# door_light.net
KiCad netlist of a schematic drawn in EAGLE
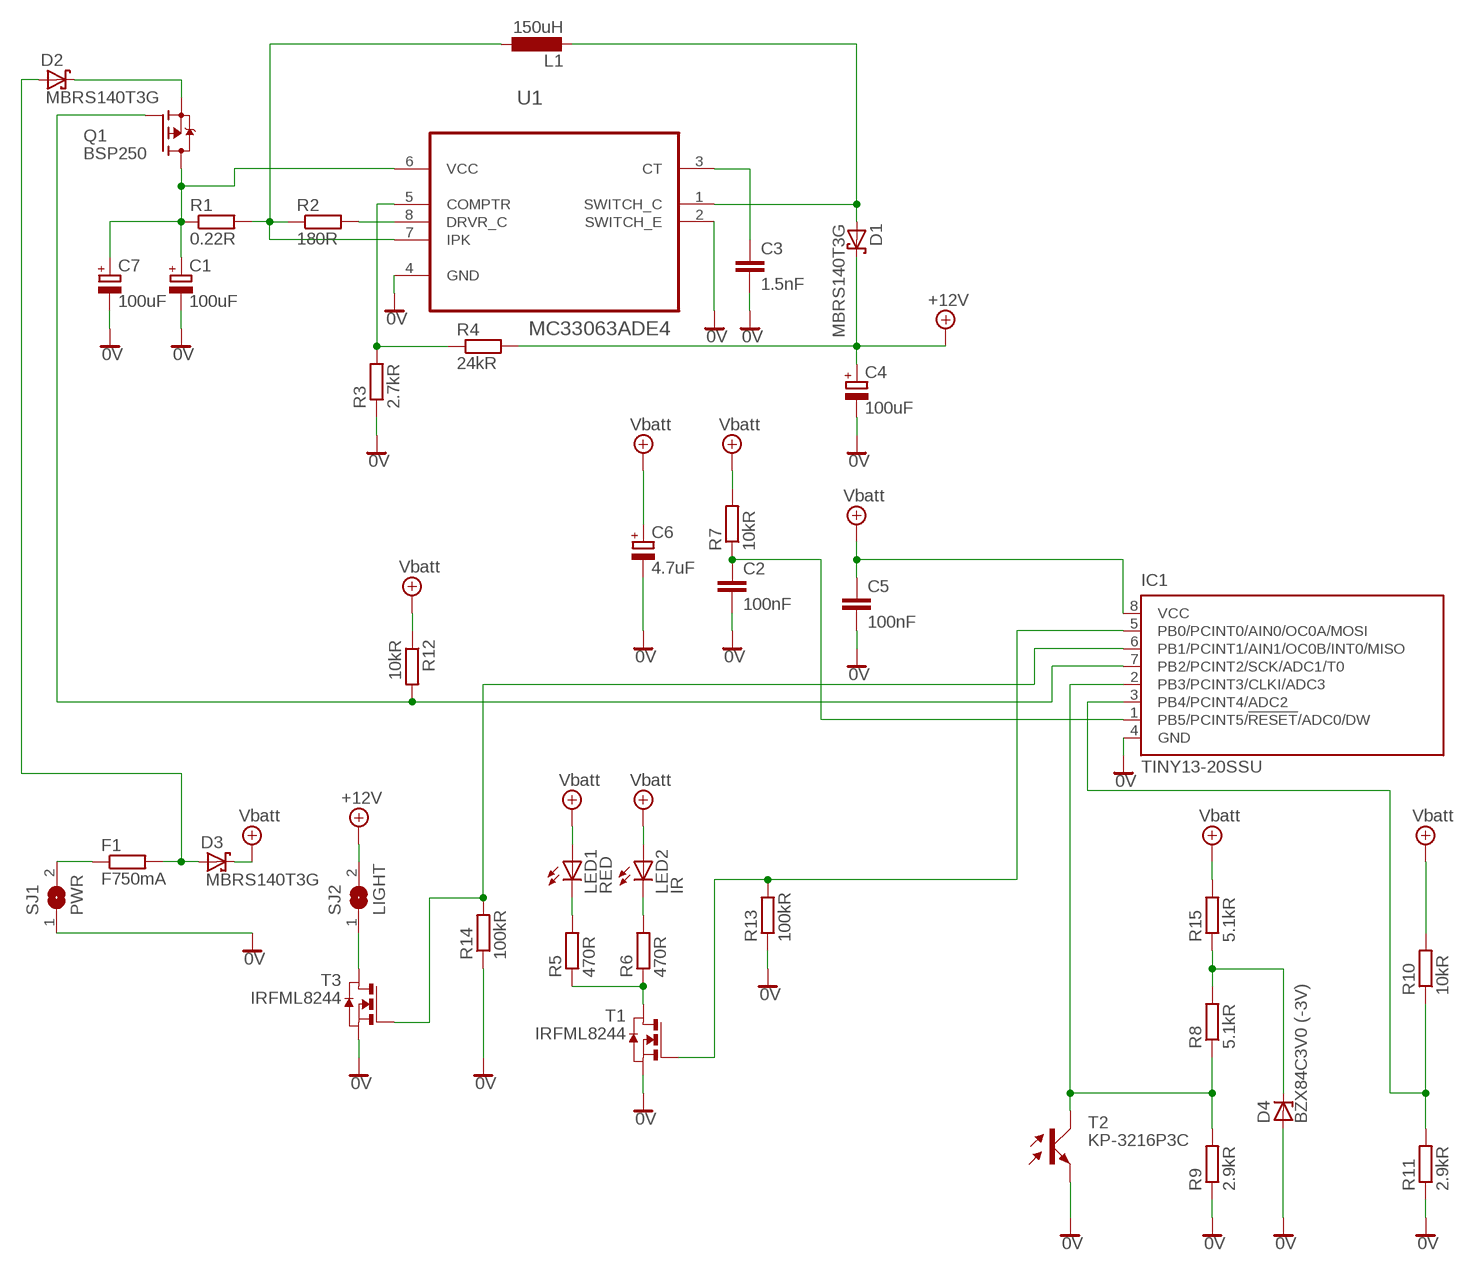
[diagram p0: schematic, sheet 1]

(export (version "E")
  (design (tool "Eeschema 10.0.6"))
  (components
    (comp (ref "C1")
      (value "100uF")
      (footprint "eagle-import:153CLV-0810")
      (libsource (lib "eagle-import") (part "CPOL-EU153CLV-0810"))
    )
    (comp (ref "C2")
      (value "100nF")
      (footprint "eagle-import:C1206")
      (libsource (lib "eagle-import") (part "C-EUC1206"))
    )
    (comp (ref "C3")
      (value "1.5nF")
      (footprint "eagle-import:C1206")
      (libsource (lib "eagle-import") (part "C-EUC1206"))
    )
    (comp (ref "C4")
      (value "100uF")
      (footprint "eagle-import:153CLV-0810")
      (libsource (lib "eagle-import") (part "CPOL-EU153CLV-0810"))
    )
    (comp (ref "C5")
      (value "100nF")
      (footprint "eagle-import:C1206")
      (libsource (lib "eagle-import") (part "C-EUC1206"))
    )
    (comp (ref "C6")
      (value "4.7uF")
      (footprint "eagle-import:153CLV-0405")
      (libsource (lib "eagle-import") (part "CPOL-EU153CLV-0405"))
    )
    (comp (ref "C7")
      (value "100uF")
      (footprint "eagle-import:153CLV-0810")
      (libsource (lib "eagle-import") (part "CPOL-EU153CLV-0810"))
    )
    (comp (ref "D1")
      (value "MBRS140T3G")
      (footprint "eagle-import:SMB")
      (libsource (lib "eagle-import") (part "MBRS130LT3"))
    )
    (comp (ref "D2")
      (value "MBRS140T3G")
      (footprint "eagle-import:SMB")
      (libsource (lib "eagle-import") (part "MBRS130LT3"))
    )
    (comp (ref "D3")
      (value "MBRS140T3G")
      (footprint "eagle-import:SMB")
      (libsource (lib "eagle-import") (part "MBRS130LT3"))
    )
    (comp (ref "D4")
      (value "BZX84C3V0 (-3V)")
      (footprint "eagle-import:TO236")
      (libsource (lib "eagle-import") (part "BZX84CSMD"))
    )
    (comp (ref "F1")
      (value "F750mA")
      (footprint "eagle-import:MINI_MELF-0207W")
      (libsource (lib "eagle-import") (part "R-EU_MELF0207W"))
    )
    (comp (ref "IC1")
      (value "TINY13-20SSU")
      (footprint "eagle-import:8S1")
      (fields (field (name "MPN") "ATTINY13-20SSU"))
      (libsource (lib "eagle-import") (part "TINY13SSU-20"))
    )
    (comp (ref "L1")
      (value "150uH")
      (footprint "eagle-import:PIS2816")
      (libsource (lib "eagle-import") (part "L-EUPIS2816"))
    )
    (comp (ref "LED1")
      (value "RED")
      (footprint "eagle-import:CHIPLED_0603")
      (libsource (lib "eagle-import") (part "LEDCHIPLED_0603"))
    )
    (comp (ref "LED2")
      (value "IR")
      (footprint "eagle-import:CHIPLED_1206")
      (libsource (lib "eagle-import") (part "LEDCHIPLED_1206"))
    )
    (comp (ref "Q1")
      (value "BSP250")
      (footprint "eagle-import:SOT223")
      (libsource (lib "eagle-import") (part "BSP170P"))
    )
    (comp (ref "R1")
      (value "0.22R")
      (footprint "eagle-import:M1206")
      (libsource (lib "eagle-import") (part "R-EU_M1206"))
    )
    (comp (ref "R2")
      (value "180R")
      (footprint "eagle-import:R0603")
      (libsource (lib "eagle-import") (part "R-EU_R0603"))
    )
    (comp (ref "R3")
      (value "2.7kR")
      (footprint "eagle-import:R0603")
      (libsource (lib "eagle-import") (part "R-EU_R0603"))
    )
    (comp (ref "R4")
      (value "24kR")
      (footprint "eagle-import:R0603")
      (libsource (lib "eagle-import") (part "R-EU_R0603"))
    )
    (comp (ref "R5")
      (value "470R")
      (footprint "eagle-import:R0603")
      (libsource (lib "eagle-import") (part "R-EU_R0603"))
    )
    (comp (ref "R6")
      (value "470R")
      (footprint "eagle-import:R0603")
      (libsource (lib "eagle-import") (part "R-EU_R0603"))
    )
    (comp (ref "R7")
      (value "10kR")
      (footprint "eagle-import:R0603")
      (libsource (lib "eagle-import") (part "R-EU_R0603"))
    )
    (comp (ref "R8")
      (value "5.1kR")
      (footprint "eagle-import:R0603")
      (libsource (lib "eagle-import") (part "R-EU_R0603"))
    )
    (comp (ref "R9")
      (value "2.9kR")
      (footprint "eagle-import:R0603")
      (libsource (lib "eagle-import") (part "R-EU_R0603"))
    )
    (comp (ref "R10")
      (value "10kR")
      (footprint "eagle-import:R0603")
      (libsource (lib "eagle-import") (part "R-EU_R0603"))
    )
    (comp (ref "R11")
      (value "2.9kR")
      (footprint "eagle-import:R0603")
      (libsource (lib "eagle-import") (part "R-EU_R0603"))
    )
    (comp (ref "R12")
      (value "10kR")
      (footprint "eagle-import:R0603")
      (libsource (lib "eagle-import") (part "R-EU_R0603"))
    )
    (comp (ref "R13")
      (value "100kR")
      (footprint "eagle-import:R0603")
      (libsource (lib "eagle-import") (part "R-EU_R0603"))
    )
    (comp (ref "R14")
      (value "100kR")
      (footprint "eagle-import:R0603")
      (libsource (lib "eagle-import") (part "R-EU_R0603"))
    )
    (comp (ref "R15")
      (value "5.1kR")
      (footprint "eagle-import:R0603")
      (libsource (lib "eagle-import") (part "R-EU_R0603"))
    )
    (comp (ref "SJ1")
      (value "PWR")
      (footprint "eagle-import:SJW")
      (libsource (lib "eagle-import") (part "SJW"))
    )
    (comp (ref "SJ2")
      (value "LIGHT")
      (footprint "eagle-import:SJW")
      (libsource (lib "eagle-import") (part "SJW"))
    )
    (comp (ref "T1")
      (value "IRFML8244")
      (footprint "eagle-import:SOT-23")
      (libsource (lib "eagle-import") (part "NMOSSOT23"))
    )
    (comp (ref "T2")
      (value "KP-3216P3C")
      (footprint "eagle-import:OPTO-TRANS-SIEMENS_BP103")
      (libsource (lib "eagle-import") (part "KP-3216P3C"))
    )
    (comp (ref "T3")
      (value "IRFML8244")
      (footprint "eagle-import:SOT-23")
      (libsource (lib "eagle-import") (part "NMOSSOT23"))
    )
    (comp (ref "U1")
      (value "MC33063ADE4")
      (footprint "eagle-import:SOIC127P600X175-8N")
      (libsource (lib "eagle-import") (part "MC33063ADE4"))
    )
  )
  (nets
    (net (code "1") (name "+12V") (class "Default")
      (node (ref "C4") (pin "+") (pinfunction "+_+") (pintype "passive"))
      (node (ref "D1") (pin "C") (pinfunction "C_C") (pintype "passive"))
      (node (ref "R4") (pin "2") (pinfunction "2_2") (pintype "passive"))
      (node (ref "SJ2") (pin "2") (pinfunction "2_2") (pintype "passive"))
    )
    (net (code "2") (name "0V") (class "Default")
      (node (ref "C1") (pin "-") (pinfunction "-_-") (pintype "passive"))
      (node (ref "C2") (pin "2") (pinfunction "2_2") (pintype "passive"))
      (node (ref "C3") (pin "2") (pinfunction "2_2") (pintype "passive"))
      (node (ref "C4") (pin "-") (pinfunction "-_-") (pintype "passive"))
      (node (ref "C5") (pin "2") (pinfunction "2_2") (pintype "passive"))
      (node (ref "C6") (pin "-") (pinfunction "-_-") (pintype "passive"))
      (node (ref "C7") (pin "-") (pinfunction "-_-") (pintype "passive"))
      (node (ref "D4") (pin "A") (pinfunction "A_A") (pintype "passive"))
      (node (ref "IC1") (pin "4") (pinfunction "GND_4") (pintype "power_in"))
      (node (ref "R11") (pin "1") (pinfunction "1_1") (pintype "passive"))
      (node (ref "R13") (pin "1") (pinfunction "1_1") (pintype "passive"))
      (node (ref "R14") (pin "1") (pinfunction "1_1") (pintype "passive"))
      (node (ref "R3") (pin "1") (pinfunction "1_1") (pintype "passive"))
      (node (ref "R9") (pin "1") (pinfunction "1_1") (pintype "passive"))
      (node (ref "SJ1") (pin "1") (pinfunction "1_1") (pintype "passive"))
      (node (ref "T1") (pin "2") (pinfunction "S_2") (pintype "passive"))
      (node (ref "T2") (pin "EMITER") (pinfunction "E_EMITER") (pintype "passive"))
      (node (ref "T3") (pin "2") (pinfunction "S_2") (pintype "passive"))
      (node (ref "U1") (pin "2") (pinfunction "SWITCH_E_2") (pintype "passive"))
      (node (ref "U1") (pin "4") (pinfunction "GND_4") (pintype "passive"))
    )
    (net (code "3") (name "Net-(D2-PadA)") (class "Default")
      (node (ref "D2") (pin "A") (pinfunction "A_A") (pintype "passive"))
      (node (ref "D3") (pin "A") (pinfunction "A_A") (pintype "passive"))
      (node (ref "F1") (pin "2") (pinfunction "2_2") (pintype "passive"))
    )
    (net (code "4") (name "Net-(D4-PadC)") (class "Default")
      (node (ref "D4") (pin "C") (pinfunction "C_C") (pintype "passive"))
      (node (ref "R15") (pin "1") (pinfunction "1_1") (pintype "passive"))
      (node (ref "R8") (pin "2") (pinfunction "2_2") (pintype "passive"))
    )
    (net (code "5") (name "Net-(F1-Pad1)") (class "Default")
      (node (ref "F1") (pin "1") (pinfunction "1_1") (pintype "passive"))
      (node (ref "SJ1") (pin "2") (pinfunction "2_2") (pintype "passive"))
    )
    (net (code "6") (name "Net-(IC1-PB0{slash}PCINT0{slash}AIN0{slash}OC0A{slash}MOSI)") (class "Default")
      (node (ref "IC1") (pin "5") (pinfunction "PB0/PCINT0/AIN0/OC0A/MOSI_5") (pintype "bidirectional"))
      (node (ref "R13") (pin "2") (pinfunction "2_2") (pintype "passive"))
      (node (ref "T1") (pin "3") (pinfunction "G_3") (pintype "passive"))
    )
    (net (code "7") (name "Net-(IC1-PB1{slash}PCINT1{slash}AIN1{slash}OC0B{slash}INT0{slash}MISO)") (class "Default")
      (node (ref "IC1") (pin "6") (pinfunction "PB1/PCINT1/AIN1/OC0B/INT0/MISO_6") (pintype "bidirectional"))
      (node (ref "R14") (pin "2") (pinfunction "2_2") (pintype "passive"))
      (node (ref "T3") (pin "3") (pinfunction "G_3") (pintype "passive"))
    )
    (net (code "8") (name "Net-(IC1-PB2{slash}PCINT2{slash}SCK{slash}ADC1{slash}T0)") (class "Default")
      (node (ref "IC1") (pin "7") (pinfunction "PB2/PCINT2/SCK/ADC1/T0_7") (pintype "bidirectional"))
      (node (ref "Q1") (pin "1") (pinfunction "G_1") (pintype "passive"))
      (node (ref "R12") (pin "2") (pinfunction "2_2") (pintype "passive"))
    )
    (net (code "9") (name "Net-(IC1-PB3{slash}PCINT3{slash}CLKI{slash}ADC3)") (class "Default")
      (node (ref "IC1") (pin "2") (pinfunction "PB3/PCINT3/CLKI/ADC3_2") (pintype "bidirectional"))
      (node (ref "R8") (pin "1") (pinfunction "1_1") (pintype "passive"))
      (node (ref "R9") (pin "2") (pinfunction "2_2") (pintype "passive"))
      (node (ref "T2") (pin "COLLECTOR") (pinfunction "C_COLLECTOR") (pintype "passive"))
    )
    (net (code "10") (name "Net-(IC1-PB4{slash}PCINT4{slash}ADC2)") (class "Default")
      (node (ref "IC1") (pin "3") (pinfunction "PB4/PCINT4/ADC2_3") (pintype "bidirectional"))
      (node (ref "R10") (pin "1") (pinfunction "1_1") (pintype "passive"))
      (node (ref "R11") (pin "2") (pinfunction "2_2") (pintype "passive"))
    )
    (net (code "11") (name "Net-(IC1-PB5{slash}PCINT5{slash}~{RESET}{slash}ADC0{slash}DW)") (class "Default")
      (node (ref "C2") (pin "1") (pinfunction "1_1") (pintype "passive"))
      (node (ref "IC1") (pin "1") (pinfunction "PB5/PCINT5/~{RESET}/ADC0/DW_1") (pintype "bidirectional"))
      (node (ref "R7") (pin "1") (pinfunction "1_1") (pintype "passive"))
    )
    (net (code "12") (name "Net-(LED1-PadC)") (class "Default")
      (node (ref "LED1") (pin "C") (pinfunction "C_C") (pintype "passive"))
      (node (ref "R5") (pin "2") (pinfunction "2_2") (pintype "passive"))
    )
    (net (code "13") (name "Net-(LED2-PadC)") (class "Default")
      (node (ref "LED2") (pin "C") (pinfunction "C_C") (pintype "passive"))
      (node (ref "R6") (pin "2") (pinfunction "2_2") (pintype "passive"))
    )
    (net (code "14") (name "Net-(Q1-S)") (class "Default")
      (node (ref "D2") (pin "C") (pinfunction "C_C") (pintype "passive"))
      (node (ref "Q1") (pin "3") (pinfunction "S_3") (pintype "passive"))
    )
    (net (code "15") (name "Net-(T1-D)") (class "Default")
      (node (ref "R5") (pin "1") (pinfunction "1_1") (pintype "passive"))
      (node (ref "R6") (pin "1") (pinfunction "1_1") (pintype "passive"))
      (node (ref "T1") (pin "1") (pinfunction "D_1") (pintype "passive"))
    )
    (net (code "16") (name "Net-(T3-D)") (class "Default")
      (node (ref "SJ2") (pin "1") (pinfunction "1_1") (pintype "passive"))
      (node (ref "T3") (pin "1") (pinfunction "D_1") (pintype "passive"))
    )
    (net (code "17") (name "Net-(U1-COMPTR)") (class "Default")
      (node (ref "R3") (pin "2") (pinfunction "2_2") (pintype "passive"))
      (node (ref "R4") (pin "1") (pinfunction "1_1") (pintype "passive"))
      (node (ref "U1") (pin "5") (pinfunction "COMPTR_5") (pintype "passive"))
    )
    (net (code "18") (name "Net-(U1-CT)") (class "Default")
      (node (ref "C3") (pin "1") (pinfunction "1_1") (pintype "passive"))
      (node (ref "U1") (pin "3") (pinfunction "CT_3") (pintype "passive"))
    )
    (net (code "19") (name "Net-(U1-DRVR_C)") (class "Default")
      (node (ref "R2") (pin "2") (pinfunction "2_2") (pintype "passive"))
      (node (ref "U1") (pin "8") (pinfunction "DRVR_C_8") (pintype "passive"))
    )
    (net (code "20") (name "Net-(U1-IPK)") (class "Default")
      (node (ref "L1") (pin "1") (pinfunction "1_1") (pintype "passive"))
      (node (ref "R1") (pin "2") (pinfunction "2_2") (pintype "passive"))
      (node (ref "R2") (pin "1") (pinfunction "1_1") (pintype "passive"))
      (node (ref "U1") (pin "7") (pinfunction "IPK_7") (pintype "passive"))
    )
    (net (code "21") (name "Net-(U1-SWITCH_C)") (class "Default")
      (node (ref "D1") (pin "A") (pinfunction "A_A") (pintype "passive"))
      (node (ref "L1") (pin "2") (pinfunction "2_2") (pintype "passive"))
      (node (ref "U1") (pin "1") (pinfunction "SWITCH_C_1") (pintype "passive"))
    )
    (net (code "22") (name "Net-(U1-VCC)") (class "Default")
      (node (ref "C1") (pin "+") (pinfunction "+_+") (pintype "passive"))
      (node (ref "C7") (pin "+") (pinfunction "+_+") (pintype "passive"))
      (node (ref "Q1") (pin "2") (pinfunction "D_2") (pintype "passive"))
      (node (ref "Q1") (pin "4") (pinfunction "D_4") (pintype "passive"))
      (node (ref "R1") (pin "1") (pinfunction "1_1") (pintype "passive"))
      (node (ref "U1") (pin "6") (pinfunction "VCC_6") (pintype "power_in"))
    )
    (net (code "23") (name "Vbatt") (class "Default")
      (node (ref "C5") (pin "1") (pinfunction "1_1") (pintype "passive"))
      (node (ref "C6") (pin "+") (pinfunction "+_+") (pintype "passive"))
      (node (ref "D3") (pin "C") (pinfunction "C_C") (pintype "passive"))
      (node (ref "IC1") (pin "8") (pinfunction "VCC_8") (pintype "power_in"))
      (node (ref "LED1") (pin "A") (pinfunction "A_A") (pintype "passive"))
      (node (ref "LED2") (pin "A") (pinfunction "A_A") (pintype "passive"))
      (node (ref "R10") (pin "2") (pinfunction "2_2") (pintype "passive"))
      (node (ref "R12") (pin "1") (pinfunction "1_1") (pintype "passive"))
      (node (ref "R15") (pin "2") (pinfunction "2_2") (pintype "passive"))
      (node (ref "R7") (pin "2") (pinfunction "2_2") (pintype "passive"))
    )
  )
)
